# TIDA-01576_ADS8686S_ISO_Interface_Pg7-Co.net
KiCad netlist of a schematic drawn in Altium Designer
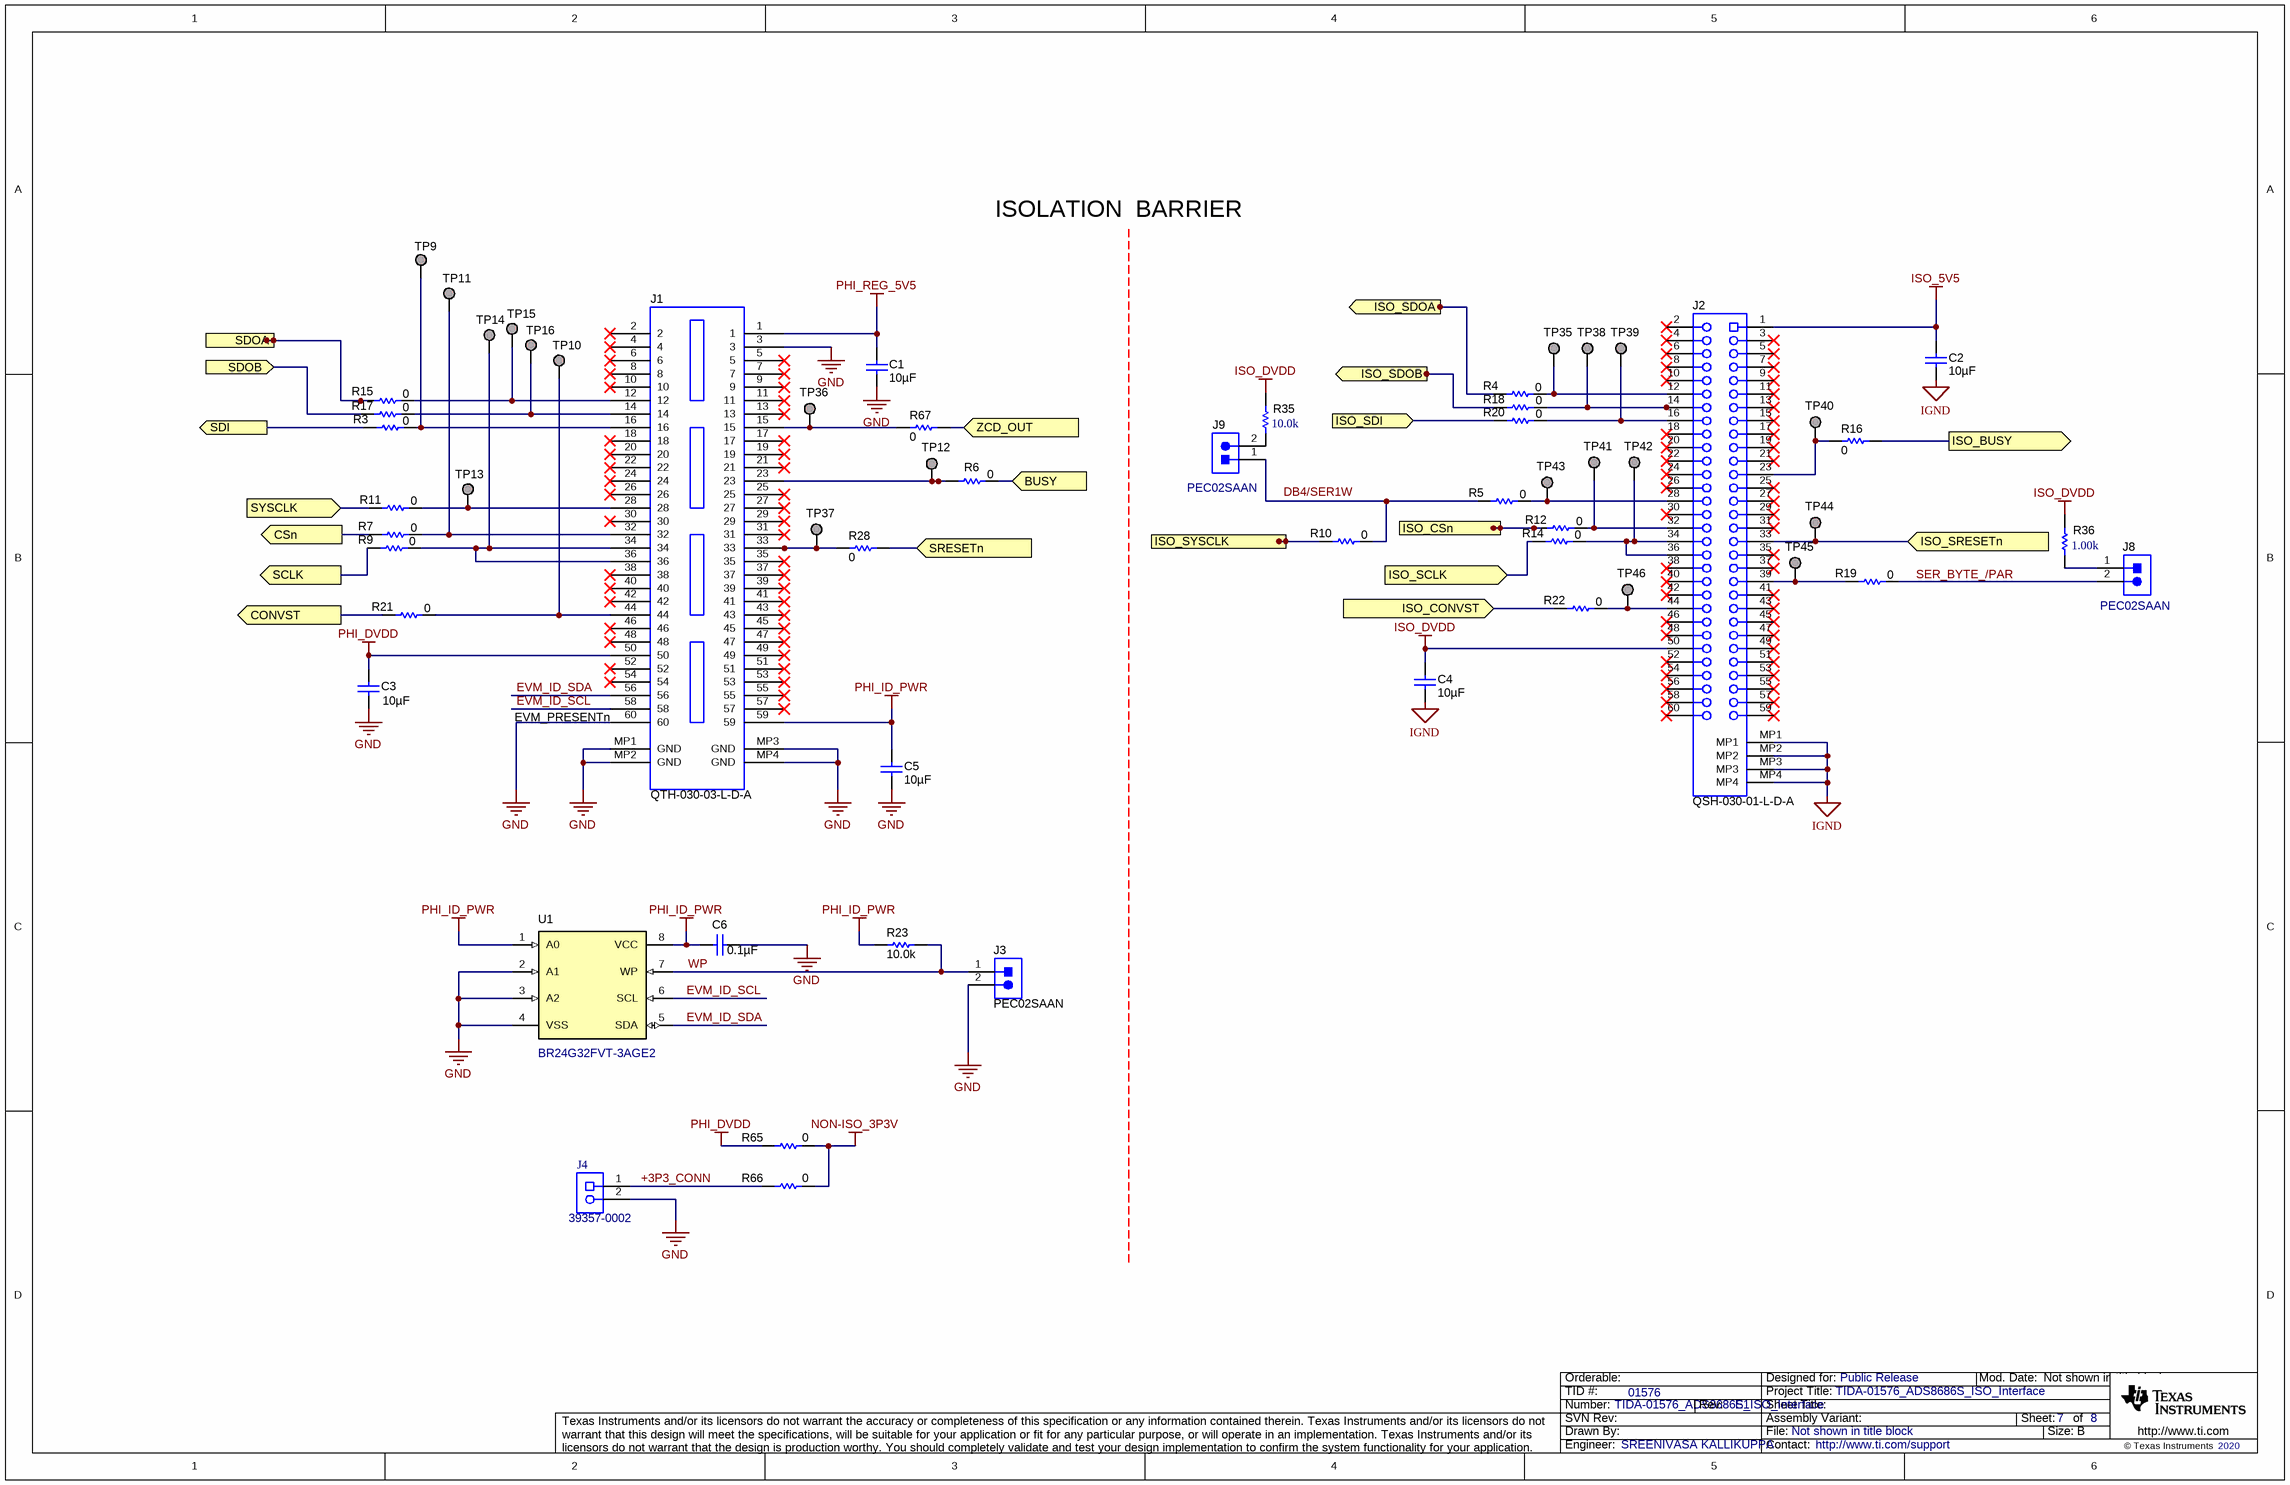
[diagram p0: TIDA-01576_ADS8686S_ISO_Interface_Pg7-Connectors.SchDoc]

(export (version "E")
  (design (tool "Eeschema 10.0.6"))
  (components
    (comp (ref "C1")
      (value "GRM21BR71A106KE51L")
      (footprint "0805_HV")
      (description "CAP, CERM, 10 µF, 10 V, +/- 10%, X7R, 0805")
      (fields
        (field (name "VALUEDISPLAYED") "10µF")
        (field (name "MANUFACTURER") "MuRata")
        (field (name "PUBLISHER") "Texas Instruments")
      )
      (libsource (lib "Capacitor_Ceramic") (part "GRM21BR71A106KE51L"))
    )
    (comp (ref "C2")
      (value "GRM21BR71A106KE51L")
      (footprint "0805_HV")
      (description "CAP, CERM, 10 µF, 10 V, +/- 10%, X7R, 0805")
      (fields
        (field (name "VALUEDISPLAYED") "10µF")
        (field (name "MANUFACTURER") "MuRata")
        (field (name "PUBLISHER") "Texas Instruments")
      )
      (libsource (lib "Capacitor_Ceramic") (part "GRM21BR71A106KE51L"))
    )
    (comp (ref "C3")
      (value "GRM21BR71A106KE51L")
      (footprint "0805_HV")
      (description "CAP, CERM, 10 µF, 10 V, +/- 10%, X7R, 0805")
      (fields
        (field (name "VALUEDISPLAYED") "10µF")
        (field (name "MANUFACTURER") "MuRata")
        (field (name "PUBLISHER") "Texas Instruments")
      )
      (libsource (lib "Capacitor_Ceramic") (part "GRM21BR71A106KE51L"))
    )
    (comp (ref "C4")
      (value "GRM21BR71A106KE51L")
      (footprint "0805_HV")
      (description "CAP, CERM, 10 µF, 10 V, +/- 10%, X7R, 0805")
      (fields
        (field (name "VALUEDISPLAYED") "10µF")
        (field (name "MANUFACTURER") "MuRata")
        (field (name "PUBLISHER") "Texas Instruments")
      )
      (libsource (lib "Capacitor_Ceramic") (part "GRM21BR71A106KE51L"))
    )
    (comp (ref "C5")
      (value "GRM21BR71A106KE51L")
      (footprint "0805_HV")
      (description "CAP, CERM, 10 µF, 10 V, +/- 10%, X7R, 0805")
      (fields
        (field (name "VALUEDISPLAYED") "10µF")
        (field (name "MANUFACTURER") "MuRata")
        (field (name "PUBLISHER") "Texas Instruments")
      )
      (libsource (lib "Capacitor_Ceramic") (part "GRM21BR71A106KE51L"))
    )
    (comp (ref "C6")
      (value "GRM155R71C104KA88D")
      (footprint "0402")
      (description "CAP, CERM, 0.1 µF, 16 V, +/- 10%, X7R, 0402")
      (fields
        (field (name "VALUEDISPLAYED") "0.1µF")
        (field (name "MANUFACTURER") "MuRata")
        (field (name "PUBLISHER") "Texas Instruments")
      )
      (libsource (lib "Capacitor_Ceramic") (part "GRM155R71C104KA88D"))
    )
    (comp (ref "J1")
      (value "QTH-030-03-L-D-A")
      (footprint "Samtec_QTH-030-01-x-D-A")
      (description "Header(Shrouded), 19.7mil, 30x2, Gold, SMT")
      (fields
        (field (name "MANUFACTURER") "Samtec")
        (field (name "SYMBOLCREATOR") "Altium")
        (field (name "PUBLISHER") "Texas Instruments")
      )
      (libsource (lib "Connectors_Samtec") (part "QTH-030-01-L-D-A"))
    )
    (comp (ref "J2")
      (value "QSH-030-01-L-D-A")
      (footprint "Samtec_QSH-030-01-X-D-A")
      (description "Receptacle, 0.5 mm, 30x2, Gold, TH")
      (fields
        (field (name "MANUFACTURER") "Samtec")
        (field (name "SYMBOLCREATOR") "Altium")
        (field (name "PUBLISHER") "Texas Instruments")
      )
      (libsource (lib "Connectors_Samtec") (part "QSH-030-01-L-D-A"))
    )
    (comp (ref "J3")
      (value "PEC02SAAN")
      (footprint "CONN_PEC02SAAN")
      (description "Header, 100mil, 2x1, Tin, TH")
      (fields
        (field (name "MANUFACTURER") "Sullins Connector Solutions")
        (field (name "SYMBOLCREATOR") "a0412235")
        (field (name "PUBLISHER") "Texas Instruments")
      )
      (libsource (lib "Connectors_Sullins") (part "PEC02SAAN"))
    )
    (comp (ref "J4")
      (value "39357-0002")
      (footprint "MOLEX_39357-0002")
      (description "Terminal Block, 3.5 mm, 2x1, Tin, TH")
      (fields (field (name "MANUFACTURER") "Molex") (field (name "PUBLISHER") "Texas Instruments"))
      (libsource (lib "Altium Vault - TI") (part "Receptacle_2x1"))
    )
    (comp (ref "J8")
      (value "PEC02SAAN")
      (footprint "CONN_PEC02SAAN")
      (description "Header, 100mil, 2x1, Tin, TH")
      (fields
        (field (name "MANUFACTURER") "Sullins Connector Solutions")
        (field (name "PUBLISHER") "Texas Instruments")
      )
      (libsource (lib "Altium Vault - TI") (part "Header_2x1"))
    )
    (comp (ref "J9")
      (value "PEC02SAAN")
      (footprint "CONN_PEC02SAAN")
      (description "Header, 100mil, 2x1, Tin, TH")
      (fields
        (field (name "MANUFACTURER") "Sullins Connector Solutions")
        (field (name "PUBLISHER") "Texas Instruments")
      )
      (libsource (lib "") (part "Header_2x1_1"))
    )
    (comp (ref "R3")
      (value "ERJ-2GE0R00X")
      (footprint "0402")
      (description "RES, 0, 5%, 0.063 W, 0402")
      (fields
        (field (name "VALUEDISPLAYED") "0")
        (field (name "MANUFACTURER") "Panasonic")
        (field (name "PUBLISHER") "Texas Instruments")
      )
      (libsource (lib "Resistor_0402") (part "ERJ-2GE0R00X"))
    )
    (comp (ref "R4")
      (value "ERJ-2GE0R00X")
      (footprint "0402")
      (description "RES, 0, 5%, 0.063 W, 0402")
      (fields
        (field (name "VALUEDISPLAYED") "0")
        (field (name "MANUFACTURER") "Panasonic")
        (field (name "PUBLISHER") "Texas Instruments")
      )
      (libsource (lib "Resistor_0402") (part "ERJ-2GE0R00X"))
    )
    (comp (ref "R5")
      (value "ERJ-2GE0R00X")
      (footprint "0402")
      (description "RES, 0, 5%, 0.063 W, 0402")
      (fields
        (field (name "VALUEDISPLAYED") "0")
        (field (name "MANUFACTURER") "Panasonic")
        (field (name "PUBLISHER") "Texas Instruments")
      )
      (libsource (lib "Resistor_0402") (part "ERJ-2GE0R00X"))
    )
    (comp (ref "R6")
      (value "ERJ-2GE0R00X")
      (footprint "0402")
      (description "RES, 0, 5%, 0.063 W, 0402")
      (fields
        (field (name "VALUEDISPLAYED") "0")
        (field (name "MANUFACTURER") "Panasonic")
        (field (name "PUBLISHER") "Texas Instruments")
      )
      (libsource (lib "Resistor_0402") (part "ERJ-2GE0R00X"))
    )
    (comp (ref "R7")
      (value "ERJ-2GE0R00X")
      (footprint "0402")
      (description "RES, 0, 5%, 0.063 W, 0402")
      (fields
        (field (name "VALUEDISPLAYED") "0")
        (field (name "MANUFACTURER") "Panasonic")
        (field (name "PUBLISHER") "Texas Instruments")
      )
      (libsource (lib "Resistor_0402") (part "ERJ-2GE0R00X"))
    )
    (comp (ref "R9")
      (value "ERJ-2GE0R00X")
      (footprint "0402")
      (description "RES, 0, 5%, 0.063 W, 0402")
      (fields
        (field (name "VALUEDISPLAYED") "0")
        (field (name "MANUFACTURER") "Panasonic")
        (field (name "PUBLISHER") "Texas Instruments")
      )
      (libsource (lib "Resistor_0402") (part "ERJ-2GE0R00X"))
    )
    (comp (ref "R10")
      (value "ERJ-2GE0R00X")
      (footprint "0402")
      (description "RES, 0, 5%, 0.063 W, 0402")
      (fields
        (field (name "VALUEDISPLAYED") "0")
        (field (name "MANUFACTURER") "Panasonic")
        (field (name "PUBLISHER") "Texas Instruments")
      )
      (libsource (lib "Resistor_0402") (part "ERJ-2GE0R00X"))
    )
    (comp (ref "R11")
      (value "ERJ-2GE0R00X")
      (footprint "0402")
      (description "RES, 0, 5%, 0.063 W, 0402")
      (fields
        (field (name "VALUEDISPLAYED") "0")
        (field (name "MANUFACTURER") "Panasonic")
        (field (name "PUBLISHER") "Texas Instruments")
      )
      (libsource (lib "Resistor_0402") (part "ERJ-2GE0R00X"))
    )
    (comp (ref "R12")
      (value "ERJ-2GE0R00X")
      (footprint "0402")
      (description "RES, 0, 5%, 0.063 W, 0402")
      (fields
        (field (name "VALUEDISPLAYED") "0")
        (field (name "MANUFACTURER") "Panasonic")
        (field (name "PUBLISHER") "Texas Instruments")
      )
      (libsource (lib "Resistor_0402") (part "ERJ-2GE0R00X"))
    )
    (comp (ref "R14")
      (value "ERJ-2GE0R00X")
      (footprint "0402")
      (description "RES, 0, 5%, 0.063 W, 0402")
      (fields
        (field (name "VALUEDISPLAYED") "0")
        (field (name "MANUFACTURER") "Panasonic")
        (field (name "PUBLISHER") "Texas Instruments")
      )
      (libsource (lib "Resistor_0402") (part "ERJ-2GE0R00X"))
    )
    (comp (ref "R15")
      (value "ERJ-2GE0R00X")
      (footprint "0402")
      (description "RES, 0, 5%, 0.063 W, 0402")
      (fields
        (field (name "VALUEDISPLAYED") "0")
        (field (name "MANUFACTURER") "Panasonic")
        (field (name "PUBLISHER") "Texas Instruments")
      )
      (libsource (lib "Resistor_0402") (part "ERJ-2GE0R00X"))
    )
    (comp (ref "R16")
      (value "ERJ-2GE0R00X")
      (footprint "0402")
      (description "RES, 0, 5%, 0.063 W, 0402")
      (fields
        (field (name "VALUEDISPLAYED") "0")
        (field (name "MANUFACTURER") "Panasonic")
        (field (name "PUBLISHER") "Texas Instruments")
      )
      (libsource (lib "Resistor_0402") (part "ERJ-2GE0R00X"))
    )
    (comp (ref "R17")
      (value "ERJ-2GE0R00X")
      (footprint "0402")
      (description "RES, 0, 5%, 0.063 W, 0402")
      (fields
        (field (name "VALUEDISPLAYED") "0")
        (field (name "MANUFACTURER") "Panasonic")
        (field (name "PUBLISHER") "Texas Instruments")
      )
      (libsource (lib "Resistor_0402") (part "ERJ-2GE0R00X"))
    )
    (comp (ref "R18")
      (value "ERJ-2GE0R00X")
      (footprint "0402")
      (description "RES, 0, 5%, 0.063 W, 0402")
      (fields
        (field (name "VALUEDISPLAYED") "0")
        (field (name "MANUFACTURER") "Panasonic")
        (field (name "PUBLISHER") "Texas Instruments")
      )
      (libsource (lib "Resistor_0402") (part "ERJ-2GE0R00X"))
    )
    (comp (ref "R19")
      (value "ERJ-2GE0R00X")
      (footprint "0402")
      (description "RES, 0, 5%, 0.063 W, 0402")
      (fields
        (field (name "VALUEDISPLAYED") "0")
        (field (name "MANUFACTURER") "Panasonic")
        (field (name "PUBLISHER") "Texas Instruments")
      )
      (libsource (lib "Resistor_0402") (part "ERJ-2GE0R00X"))
    )
    (comp (ref "R20")
      (value "ERJ-2GE0R00X")
      (footprint "0402")
      (description "RES, 0, 5%, 0.063 W, 0402")
      (fields
        (field (name "VALUEDISPLAYED") "0")
        (field (name "MANUFACTURER") "Panasonic")
        (field (name "PUBLISHER") "Texas Instruments")
      )
      (libsource (lib "Resistor_0402") (part "ERJ-2GE0R00X"))
    )
    (comp (ref "R21")
      (value "ERJ-2GE0R00X")
      (footprint "0402")
      (description "RES, 0, 5%, 0.063 W, 0402")
      (fields
        (field (name "VALUEDISPLAYED") "0")
        (field (name "MANUFACTURER") "Panasonic")
        (field (name "PUBLISHER") "Texas Instruments")
      )
      (libsource (lib "Resistor_0402") (part "ERJ-2GE0R00X"))
    )
    (comp (ref "R22")
      (value "ERJ-2GE0R00X")
      (footprint "0402")
      (description "RES, 0, 5%, 0.063 W, 0402")
      (fields
        (field (name "VALUEDISPLAYED") "0")
        (field (name "MANUFACTURER") "Panasonic")
        (field (name "PUBLISHER") "Texas Instruments")
      )
      (libsource (lib "Resistor_0402") (part "ERJ-2GE0R00X"))
    )
    (comp (ref "R23")
      (value "CRCW060310K0FKEA")
      (footprint "0603")
      (description "RES, 10.0 k, 1%, 0.1 W, 0603")
      (fields
        (field (name "VALUEDISPLAYED") "10.0k")
        (field (name "MANUFACTURER") "Vishay-Dale")
        (field (name "PUBLISHER") "Texas Instruments")
      )
      (libsource (lib "Resistor_0603") (part "CRCW060310K0FKEA"))
    )
    (comp (ref "R28")
      (value "ERJ-2GE0R00X")
      (footprint "0402")
      (description "RES, 0, 5%, 0.063 W, 0402")
      (fields
        (field (name "VALUEDISPLAYED") "0")
        (field (name "MANUFACTURER") "Panasonic")
        (field (name "PUBLISHER") "Texas Instruments")
      )
      (libsource (lib "Resistor_0402") (part "ERJ-2GE0R00X"))
    )
    (comp (ref "R35")
      (value "ERJ-2RKF1002X")
      (footprint "0402")
      (description "RES, 10.0 k, 1%, 0.1 W, 0402")
      (fields
        (field (name "MANUFACTURER") "Panasonic")
        (field (name "VALUEDISPLAYED") "10.0k")
        (field (name "PUBLISHER") "Texas Instruments")
      )
      (libsource (lib "Altium Vault - TI") (part "Resistor"))
    )
    (comp (ref "R36")
      (value "ERJ-2RKF1001X")
      (footprint "0402")
      (description "RES, 1.00 k, 1%, 0.1 W, 0402")
      (fields
        (field (name "MANUFACTURER") "Panasonic")
        (field (name "VALUEDISPLAYED") "1.00k")
        (field (name "PUBLISHER") "Texas Instruments")
      )
      (libsource (lib "Altium Vault - TI") (part "Resistor"))
    )
    (comp (ref "R65")
      (value "CRCW06030000Z0EA")
      (footprint "0603")
      (description "RES, 0, 5%, 0.1 W, 0603")
      (fields
        (field (name "VALUEDISPLAYED") "0")
        (field (name "MANUFACTURER") "Vishay-Dale")
        (field (name "PUBLISHER") "Texas Instruments")
      )
      (libsource (lib "Resistor_0603") (part "CRCW06030000Z0EA"))
    )
    (comp (ref "R66")
      (value "CRCW06030000Z0EA")
      (footprint "0603")
      (description "RES, 0, 5%, 0.1 W, 0603")
      (fields
        (field (name "VALUEDISPLAYED") "0")
        (field (name "MANUFACTURER") "Vishay-Dale")
        (field (name "PUBLISHER") "Texas Instruments")
      )
      (libsource (lib "Resistor_0603") (part "CRCW06030000Z0EA"))
    )
    (comp (ref "R67")
      (value "ERJ-2GE0R00X")
      (footprint "0402")
      (description "RES, 0, 5%, 0.063 W, 0402")
      (fields
        (field (name "VALUEDISPLAYED") "0")
        (field (name "MANUFACTURER") "Panasonic")
        (field (name "PUBLISHER") "Texas Instruments")
      )
      (libsource (lib "Resistor_0402") (part "ERJ-2GE0R00X"))
    )
    (comp (ref "TP9")
      (value "TP_H0.45P0.75")
      (footprint "TP_H045P075")
      (description "Testpoint")
      (fields
        (field (name "MANUFACTURER") "Texas Instruments")
        (field (name "SYMBOLCREATOR") "a0412235")
        (field (name "PUBLISHER") "Texas Instruments")
      )
      (libsource (lib "Hardware") (part "TP_H0.45P0.75"))
    )
    (comp (ref "TP10")
      (value "TP_H0.45P0.75")
      (footprint "TP_H045P075")
      (description "Testpoint")
      (fields
        (field (name "MANUFACTURER") "Texas Instruments")
        (field (name "SYMBOLCREATOR") "a0412235")
        (field (name "PUBLISHER") "Texas Instruments")
      )
      (libsource (lib "Hardware") (part "TP_H0.45P0.75"))
    )
    (comp (ref "TP11")
      (value "TP_H0.45P0.75")
      (footprint "TP_H045P075")
      (description "Testpoint")
      (fields
        (field (name "MANUFACTURER") "Texas Instruments")
        (field (name "SYMBOLCREATOR") "a0412235")
        (field (name "PUBLISHER") "Texas Instruments")
      )
      (libsource (lib "Hardware") (part "TP_H0.45P0.75"))
    )
    (comp (ref "TP12")
      (value "TP_H0.45P0.75")
      (footprint "TP_H045P075")
      (description "Testpoint")
      (fields
        (field (name "MANUFACTURER") "Texas Instruments")
        (field (name "SYMBOLCREATOR") "a0412235")
        (field (name "PUBLISHER") "Texas Instruments")
      )
      (libsource (lib "Hardware") (part "TP_H0.45P0.75"))
    )
    (comp (ref "TP13")
      (value "TP_H0.45P0.75")
      (footprint "TP_H045P075")
      (description "Testpoint")
      (fields
        (field (name "MANUFACTURER") "Texas Instruments")
        (field (name "SYMBOLCREATOR") "a0412235")
        (field (name "PUBLISHER") "Texas Instruments")
      )
      (libsource (lib "Hardware") (part "TP_H0.45P0.75"))
    )
    (comp (ref "TP14")
      (value "TP_H0.45P0.75")
      (footprint "TP_H045P075")
      (description "Testpoint")
      (fields
        (field (name "MANUFACTURER") "Texas Instruments")
        (field (name "SYMBOLCREATOR") "a0412235")
        (field (name "PUBLISHER") "Texas Instruments")
      )
      (libsource (lib "Hardware") (part "TP_H0.45P0.75"))
    )
    (comp (ref "TP15")
      (value "TP_H0.45P0.75")
      (footprint "TP_H045P075")
      (description "Testpoint")
      (fields
        (field (name "MANUFACTURER") "Texas Instruments")
        (field (name "SYMBOLCREATOR") "a0412235")
        (field (name "PUBLISHER") "Texas Instruments")
      )
      (libsource (lib "Hardware") (part "TP_H0.45P0.75"))
    )
    (comp (ref "TP16")
      (value "TP_H0.45P0.75")
      (footprint "TP_H045P075")
      (description "Testpoint")
      (fields
        (field (name "MANUFACTURER") "Texas Instruments")
        (field (name "SYMBOLCREATOR") "a0412235")
        (field (name "PUBLISHER") "Texas Instruments")
      )
      (libsource (lib "Hardware") (part "TP_H0.45P0.75"))
    )
    (comp (ref "TP35")
      (value "TP_H0.45P0.75")
      (footprint "TP_H045P075")
      (description "Testpoint")
      (fields
        (field (name "MANUFACTURER") "Texas Instruments")
        (field (name "SYMBOLCREATOR") "a0412235")
        (field (name "PUBLISHER") "Texas Instruments")
      )
      (libsource (lib "Hardware") (part "TP_H0.45P0.75"))
    )
    (comp (ref "TP36")
      (value "TP_H0.45P0.75")
      (footprint "TP_H045P075")
      (description "Testpoint")
      (fields
        (field (name "MANUFACTURER") "Texas Instruments")
        (field (name "SYMBOLCREATOR") "a0412235")
        (field (name "PUBLISHER") "Texas Instruments")
      )
      (libsource (lib "Hardware") (part "TP_H0.45P0.75"))
    )
    (comp (ref "TP37")
      (value "TP_H0.45P0.75")
      (footprint "TP_H045P075")
      (description "Testpoint")
      (fields
        (field (name "MANUFACTURER") "Texas Instruments")
        (field (name "SYMBOLCREATOR") "a0412235")
        (field (name "PUBLISHER") "Texas Instruments")
      )
      (libsource (lib "Hardware") (part "TP_H0.45P0.75"))
    )
    (comp (ref "TP38")
      (value "TP_H0.45P0.75")
      (footprint "TP_H045P075")
      (description "Testpoint")
      (fields
        (field (name "MANUFACTURER") "Texas Instruments")
        (field (name "SYMBOLCREATOR") "a0412235")
        (field (name "PUBLISHER") "Texas Instruments")
      )
      (libsource (lib "Hardware") (part "TP_H0.45P0.75"))
    )
    (comp (ref "TP39")
      (value "TP_H0.45P0.75")
      (footprint "TP_H045P075")
      (description "Testpoint")
      (fields
        (field (name "MANUFACTURER") "Texas Instruments")
        (field (name "SYMBOLCREATOR") "a0412235")
        (field (name "PUBLISHER") "Texas Instruments")
      )
      (libsource (lib "Hardware") (part "TP_H0.45P0.75"))
    )
    (comp (ref "TP40")
      (value "TP_H0.45P0.75")
      (footprint "TP_H045P075")
      (description "Testpoint")
      (fields
        (field (name "MANUFACTURER") "Texas Instruments")
        (field (name "SYMBOLCREATOR") "a0412235")
        (field (name "PUBLISHER") "Texas Instruments")
      )
      (libsource (lib "Hardware") (part "TP_H0.45P0.75"))
    )
    (comp (ref "TP41")
      (value "TP_H0.45P0.75")
      (footprint "TP_H045P075")
      (description "Testpoint")
      (fields
        (field (name "MANUFACTURER") "Texas Instruments")
        (field (name "SYMBOLCREATOR") "a0412235")
        (field (name "PUBLISHER") "Texas Instruments")
      )
      (libsource (lib "Hardware") (part "TP_H0.45P0.75"))
    )
    (comp (ref "TP42")
      (value "TP_H0.45P0.75")
      (footprint "TP_H045P075")
      (description "Testpoint")
      (fields
        (field (name "MANUFACTURER") "Texas Instruments")
        (field (name "SYMBOLCREATOR") "a0412235")
        (field (name "PUBLISHER") "Texas Instruments")
      )
      (libsource (lib "Hardware") (part "TP_H0.45P0.75"))
    )
    (comp (ref "TP43")
      (value "TP_H0.45P0.75")
      (footprint "TP_H045P075")
      (description "Testpoint")
      (fields
        (field (name "MANUFACTURER") "Texas Instruments")
        (field (name "SYMBOLCREATOR") "a0412235")
        (field (name "PUBLISHER") "Texas Instruments")
      )
      (libsource (lib "Hardware") (part "TP_H0.45P0.75"))
    )
    (comp (ref "TP44")
      (value "TP_H0.45P0.75")
      (footprint "TP_H045P075")
      (description "Testpoint")
      (fields
        (field (name "MANUFACTURER") "Texas Instruments")
        (field (name "SYMBOLCREATOR") "a0412235")
        (field (name "PUBLISHER") "Texas Instruments")
      )
      (libsource (lib "Hardware") (part "TP_H0.45P0.75"))
    )
    (comp (ref "TP45")
      (value "TP_H0.45P0.75")
      (footprint "TP_H045P075")
      (description "Testpoint")
      (fields
        (field (name "MANUFACTURER") "Texas Instruments")
        (field (name "SYMBOLCREATOR") "a0412235")
        (field (name "PUBLISHER") "Texas Instruments")
      )
      (libsource (lib "Hardware") (part "TP_H0.45P0.75"))
    )
    (comp (ref "TP46")
      (value "TP_H0.45P0.75")
      (footprint "TP_H045P075")
      (description "Testpoint")
      (fields
        (field (name "MANUFACTURER") "Texas Instruments")
        (field (name "SYMBOLCREATOR") "a0412235")
        (field (name "PUBLISHER") "Texas Instruments")
      )
      (libsource (lib "Hardware") (part "TP_H0.45P0.75"))
    )
    (comp (ref "U1")
      (value "BR24G32FVT-3AGE2")
      (footprint "TSOP65P640X120-8N")
      (description "I2C BUS EEPROM (2-Wire), TSSOP-B8")
      (fields (field (name "MANUFACTURER") "Rohm") (field (name "PUBLISHER") "Texas Instruments"))
      (libsource (lib "Altium Vault - TI") (part "EEPROM_8P"))
    )
  )
  (nets
    (net (code "1") (name "/+3P3_CONN") (class "Default")
      (node (ref "J4") (pin "1") (pinfunction "1_1") (pintype "passive"))
      (node (ref "R66") (pin "2") (pinfunction "2_2") (pintype "passive"))
    )
    (net (code "2") (name "/BUSY") (class "Default")
      (node (ref "R6") (pin "2") (pinfunction "2_2") (pintype "passive"))
    )
    (net (code "3") (name "/CONVST") (class "Default")
      (node (ref "R21") (pin "1") (pinfunction "1_1") (pintype "passive"))
    )
    (net (code "4") (name "/CSn") (class "Default")
      (node (ref "R7") (pin "1") (pinfunction "1_1") (pintype "passive"))
    )
    (net (code "6") (name "/EVM_ID_SCL") (class "Default")
      (node (ref "J1") (pin "58") (pinfunction "58_58") (pintype "passive"))
      (node (ref "U1") (pin "6") (pinfunction "SCL_6") (pintype "input"))
    )
    (net (code "7") (name "/EVM_ID_SDA") (class "Default")
      (node (ref "J1") (pin "56") (pinfunction "56_56") (pintype "passive"))
      (node (ref "U1") (pin "5") (pinfunction "SDA_5") (pintype "bidirectional"))
    )
    (net (code "8") (name "/ISO_BUSY") (class "Default")
      (node (ref "R16") (pin "1") (pinfunction "1_1") (pintype "passive"))
    )
    (net (code "9") (name "/ISO_CONVST") (class "Default")
      (node (ref "R22") (pin "1") (pinfunction "1_1") (pintype "passive"))
    )
    (net (code "10") (name "/ISO_CSn") (class "Default")
      (node (ref "R12") (pin "1") (pinfunction "1_1") (pintype "passive"))
    )
    (net (code "11") (name "/ISO_SCLK") (class "Default")
      (node (ref "R14") (pin "1") (pinfunction "1_1") (pintype "passive"))
    )
    (net (code "12") (name "/ISO_SDI") (class "Default")
      (node (ref "R20") (pin "1") (pinfunction "1_1") (pintype "passive"))
    )
    (net (code "13") (name "/ISO_SDOA") (class "Default")
      (node (ref "R4") (pin "1") (pinfunction "1_1") (pintype "passive"))
    )
    (net (code "14") (name "/ISO_SDOB") (class "Default")
      (node (ref "R18") (pin "1") (pinfunction "1_1") (pintype "passive"))
    )
    (net (code "15") (name "/ISO_SRESETn") (class "Default")
      (node (ref "J2") (pin "33") (pinfunction "33_33") (pintype "passive"))
      (node (ref "TP44") (pin "1") (pintype "passive"))
    )
    (net (code "16") (name "/ISO_SYSCLK") (class "Default")
      (node (ref "R10") (pin "1") (pinfunction "1_1") (pintype "passive"))
    )
    (net (code "17") (name "/SCLK") (class "Default")
      (node (ref "R9") (pin "1") (pinfunction "1_1") (pintype "passive"))
    )
    (net (code "18") (name "/SDI") (class "Default")
      (node (ref "R3") (pin "1") (pinfunction "1_1") (pintype "passive"))
    )
    (net (code "19") (name "/SDOA") (class "Default")
      (node (ref "R15") (pin "1") (pinfunction "1_1") (pintype "passive"))
    )
    (net (code "20") (name "/SDOB") (class "Default")
      (node (ref "R17") (pin "1") (pinfunction "1_1") (pintype "passive"))
    )
    (net (code "22") (name "/SRESETn") (class "Default")
      (node (ref "R28") (pin "1") (pinfunction "1_1") (pintype "passive"))
    )
    (net (code "23") (name "/SYSCLK") (class "Default")
      (node (ref "R11") (pin "1") (pinfunction "1_1") (pintype "passive"))
    )
    (net (code "24") (name "/WP") (class "Default")
      (node (ref "J3") (pin "1") (pinfunction "1_1") (pintype "passive"))
      (node (ref "R23") (pin "1") (pinfunction "1_1") (pintype "passive"))
      (node (ref "U1") (pin "7") (pinfunction "WP_7") (pintype "input"))
    )
    (net (code "25") (name "/ZCD_OUT") (class "Default")
      (node (ref "R67") (pin "1") (pinfunction "1_1") (pintype "passive"))
    )
    (net (code "26") (name "GND") (class "Default")
      (node (ref "C1") (pin "2") (pinfunction "2_2") (pintype "passive"))
      (node (ref "C3") (pin "2") (pinfunction "2_2") (pintype "passive"))
      (node (ref "C5") (pin "2") (pinfunction "2_2") (pintype "passive"))
      (node (ref "C6") (pin "1") (pinfunction "1_1") (pintype "passive"))
      (node (ref "J1") (pin "3") (pinfunction "3_3") (pintype "passive"))
      (node (ref "J1") (pin "60") (pinfunction "60_60") (pintype "passive"))
      (node (ref "J1") (pin "MP1") (pinfunction "GND_MP1") (pintype "passive"))
      (node (ref "J1") (pin "MP2") (pinfunction "GND_MP2") (pintype "passive"))
      (node (ref "J1") (pin "MP3") (pinfunction "GND_MP3") (pintype "passive"))
      (node (ref "J1") (pin "MP4") (pinfunction "GND_MP4") (pintype "passive"))
      (node (ref "J3") (pin "2") (pinfunction "2_2") (pintype "passive"))
      (node (ref "J4") (pin "2") (pinfunction "2_2") (pintype "passive"))
      (node (ref "U1") (pin "2") (pinfunction "A1_2") (pintype "input"))
      (node (ref "U1") (pin "3") (pinfunction "A2_3") (pintype "input"))
      (node (ref "U1") (pin "4") (pinfunction "VSS_4") (pintype "power_in"))
    )
    (net (code "27") (name "IGND") (class "Default")
      (node (ref "C2") (pin "2") (pinfunction "2_2") (pintype "passive"))
      (node (ref "C4") (pin "2") (pinfunction "2_2") (pintype "passive"))
      (node (ref "J2") (pin "MP1") (pinfunction "MP1_MP1") (pintype "passive"))
      (node (ref "J2") (pin "MP2") (pinfunction "MP2_MP2") (pintype "passive"))
      (node (ref "J2") (pin "MP3") (pinfunction "MP3_MP3") (pintype "passive"))
      (node (ref "J2") (pin "MP4") (pinfunction "MP4_MP4") (pintype "passive"))
    )
    (net (code "28") (name "ISO_5V5") (class "Default")
      (node (ref "C2") (pin "1") (pinfunction "1_1") (pintype "passive"))
      (node (ref "J2") (pin "1") (pinfunction "1_1") (pintype "passive"))
    )
    (net (code "29") (name "ISO_DVDD") (class "Default")
      (node (ref "C4") (pin "1") (pinfunction "1_1") (pintype "passive"))
      (node (ref "J2") (pin "50") (pinfunction "50_50") (pintype "passive"))
      (node (ref "R35") (pin "2") (pinfunction "2_2") (pintype "passive"))
      (node (ref "R36") (pin "2") (pinfunction "2_2") (pintype "passive"))
    )
    (net (code "30") (name "NON-ISO_3P3V") (class "Default")
      (node (ref "R65") (pin "1") (pinfunction "1_1") (pintype "passive"))
      (node (ref "R66") (pin "1") (pinfunction "1_1") (pintype "passive"))
    )
    (net (code "31") (name "Net-(J1-Pad12)") (class "Default")
      (node (ref "J1") (pin "12") (pinfunction "12_12") (pintype "passive"))
      (node (ref "R15") (pin "2") (pinfunction "2_2") (pintype "passive"))
      (node (ref "TP15") (pin "1") (pintype "passive"))
    )
    (net (code "32") (name "Net-(J1-Pad14)") (class "Default")
      (node (ref "J1") (pin "14") (pinfunction "14_14") (pintype "passive"))
      (node (ref "R17") (pin "2") (pinfunction "2_2") (pintype "passive"))
      (node (ref "TP16") (pin "1") (pintype "passive"))
    )
    (net (code "33") (name "Net-(J1-Pad15)") (class "Default")
      (node (ref "J1") (pin "15") (pinfunction "15_15") (pintype "passive"))
      (node (ref "R67") (pin "2") (pinfunction "2_2") (pintype "passive"))
      (node (ref "TP36") (pin "1") (pintype "passive"))
    )
    (net (code "34") (name "Net-(J1-Pad16)") (class "Default")
      (node (ref "J1") (pin "16") (pinfunction "16_16") (pintype "passive"))
      (node (ref "R3") (pin "2") (pinfunction "2_2") (pintype "passive"))
      (node (ref "TP9") (pin "1") (pintype "passive"))
    )
    (net (code "35") (name "Net-(J1-Pad23)") (class "Default")
      (node (ref "J1") (pin "23") (pinfunction "23_23") (pintype "passive"))
      (node (ref "R6") (pin "1") (pinfunction "1_1") (pintype "passive"))
      (node (ref "TP12") (pin "1") (pintype "passive"))
    )
    (net (code "36") (name "Net-(J1-Pad28)") (class "Default")
      (node (ref "J1") (pin "28") (pinfunction "28_28") (pintype "passive"))
      (node (ref "R11") (pin "2") (pinfunction "2_2") (pintype "passive"))
      (node (ref "TP13") (pin "1") (pintype "passive"))
    )
    (net (code "37") (name "Net-(J1-Pad32)") (class "Default")
      (node (ref "J1") (pin "32") (pinfunction "32_32") (pintype "passive"))
      (node (ref "R7") (pin "2") (pinfunction "2_2") (pintype "passive"))
      (node (ref "TP11") (pin "1") (pintype "passive"))
    )
    (net (code "38") (name "Net-(J1-Pad33)") (class "Default")
      (node (ref "J1") (pin "33") (pinfunction "33_33") (pintype "passive"))
      (node (ref "R28") (pin "2") (pinfunction "2_2") (pintype "passive"))
      (node (ref "TP37") (pin "1") (pintype "passive"))
    )
    (net (code "39") (name "Net-(J1-Pad34)") (class "Default")
      (node (ref "J1") (pin "34") (pinfunction "34_34") (pintype "passive"))
      (node (ref "J1") (pin "36") (pinfunction "36_36") (pintype "passive"))
      (node (ref "R9") (pin "2") (pinfunction "2_2") (pintype "passive"))
      (node (ref "TP14") (pin "1") (pintype "passive"))
    )
    (net (code "40") (name "Net-(J1-Pad44)") (class "Default")
      (node (ref "J1") (pin "44") (pinfunction "44_44") (pintype "passive"))
      (node (ref "R21") (pin "2") (pinfunction "2_2") (pintype "passive"))
      (node (ref "TP10") (pin "1") (pintype "passive"))
    )
    (net (code "41") (name "Net-(J2-Pad12)") (class "Default")
      (node (ref "J2") (pin "12") (pinfunction "12_12") (pintype "passive"))
      (node (ref "R4") (pin "2") (pinfunction "2_2") (pintype "passive"))
      (node (ref "TP35") (pin "1") (pintype "passive"))
    )
    (net (code "42") (name "Net-(J2-Pad14)") (class "Default")
      (node (ref "J2") (pin "14") (pinfunction "14_14") (pintype "passive"))
      (node (ref "R18") (pin "2") (pinfunction "2_2") (pintype "passive"))
      (node (ref "TP38") (pin "1") (pintype "passive"))
    )
    (net (code "43") (name "Net-(J2-Pad16)") (class "Default")
      (node (ref "J2") (pin "16") (pinfunction "16_16") (pintype "passive"))
      (node (ref "R20") (pin "2") (pinfunction "2_2") (pintype "passive"))
      (node (ref "TP39") (pin "1") (pintype "passive"))
    )
    (net (code "44") (name "Net-(J2-Pad23)") (class "Default")
      (node (ref "J2") (pin "23") (pinfunction "23_23") (pintype "passive"))
      (node (ref "R16") (pin "2") (pinfunction "2_2") (pintype "passive"))
      (node (ref "TP40") (pin "1") (pintype "passive"))
    )
    (net (code "45") (name "Net-(J2-Pad28)") (class "Default")
      (node (ref "J2") (pin "28") (pinfunction "28_28") (pintype "passive"))
      (node (ref "R5") (pin "2") (pinfunction "2_2") (pintype "passive"))
      (node (ref "TP43") (pin "1") (pintype "passive"))
    )
    (net (code "46") (name "Net-(J2-Pad32)") (class "Default")
      (node (ref "J2") (pin "32") (pinfunction "32_32") (pintype "passive"))
      (node (ref "R12") (pin "2") (pinfunction "2_2") (pintype "passive"))
      (node (ref "TP41") (pin "1") (pintype "passive"))
    )
    (net (code "47") (name "Net-(J2-Pad34)") (class "Default")
      (node (ref "J2") (pin "34") (pinfunction "34_34") (pintype "passive"))
      (node (ref "J2") (pin "36") (pinfunction "36_36") (pintype "passive"))
      (node (ref "R14") (pin "2") (pinfunction "2_2") (pintype "passive"))
      (node (ref "TP42") (pin "1") (pintype "passive"))
    )
    (net (code "48") (name "Net-(J2-Pad39)") (class "Default")
      (node (ref "J2") (pin "39") (pinfunction "39_39") (pintype "passive"))
      (node (ref "R19") (pin "1") (pinfunction "1_1") (pintype "passive"))
      (node (ref "TP45") (pin "1") (pintype "passive"))
    )
    (net (code "49") (name "Net-(J2-Pad44)") (class "Default")
      (node (ref "J2") (pin "44") (pinfunction "44_44") (pintype "passive"))
      (node (ref "R22") (pin "2") (pinfunction "2_2") (pintype "passive"))
      (node (ref "TP46") (pin "1") (pintype "passive"))
    )
    (net (code "50") (name "Net-(J8-Pad1)") (class "Default")
      (node (ref "J8") (pin "1") (pinfunction "1_1") (pintype "passive"))
      (node (ref "R36") (pin "1") (pinfunction "1_1") (pintype "passive"))
    )
    (net (code "51") (name "Net-(J8-Pad2)") (class "Default")
      (node (ref "J8") (pin "2") (pinfunction "2_2") (pintype "passive"))
      (node (ref "R19") (pin "2") (pinfunction "2_2") (pintype "passive"))
    )
    (net (code "52") (name "Net-(J9-Pad1)") (class "Default")
      (node (ref "J9") (pin "1") (pinfunction "1_1") (pintype "passive"))
      (node (ref "R10") (pin "2") (pinfunction "2_2") (pintype "passive"))
      (node (ref "R5") (pin "1") (pinfunction "1_1") (pintype "passive"))
    )
    (net (code "53") (name "Net-(J9-Pad2)") (class "Default")
      (node (ref "J9") (pin "2") (pinfunction "2_2") (pintype "passive"))
      (node (ref "R35") (pin "1") (pinfunction "1_1") (pintype "passive"))
    )
    (net (code "54") (name "PHI_DVDD") (class "Default")
      (node (ref "C3") (pin "1") (pinfunction "1_1") (pintype "passive"))
      (node (ref "J1") (pin "50") (pinfunction "50_50") (pintype "passive"))
      (node (ref "R65") (pin "2") (pinfunction "2_2") (pintype "passive"))
    )
    (net (code "55") (name "PHI_ID_PWR") (class "Default")
      (node (ref "C5") (pin "1") (pinfunction "1_1") (pintype "passive"))
      (node (ref "C6") (pin "2") (pinfunction "2_2") (pintype "passive"))
      (node (ref "J1") (pin "59") (pinfunction "59_59") (pintype "passive"))
      (node (ref "R23") (pin "2") (pinfunction "2_2") (pintype "passive"))
      (node (ref "U1") (pin "1") (pinfunction "A0_1") (pintype "input"))
      (node (ref "U1") (pin "8") (pinfunction "VCC_8") (pintype "power_in"))
    )
    (net (code "56") (name "PHI_REG_5V5") (class "Default")
      (node (ref "C1") (pin "1") (pinfunction "1_1") (pintype "passive"))
      (node (ref "J1") (pin "1") (pinfunction "1_1") (pintype "passive"))
    )
    (net (code "57") (name "unconnected-(J1-Pad2)") (class "Default")
      (node (ref "J1") (pin "2") (pinfunction "2_2") (pintype "passive+no_connect"))
    )
    (net (code "58") (name "unconnected-(J1-Pad4)") (class "Default")
      (node (ref "J1") (pin "4") (pinfunction "4_4") (pintype "passive+no_connect"))
    )
    (net (code "59") (name "unconnected-(J1-Pad5)") (class "Default")
      (node (ref "J1") (pin "5") (pinfunction "5_5") (pintype "passive+no_connect"))
    )
    (net (code "60") (name "unconnected-(J1-Pad6)") (class "Default")
      (node (ref "J1") (pin "6") (pinfunction "6_6") (pintype "passive+no_connect"))
    )
    (net (code "61") (name "unconnected-(J1-Pad7)") (class "Default")
      (node (ref "J1") (pin "7") (pinfunction "7_7") (pintype "passive+no_connect"))
    )
    (net (code "62") (name "unconnected-(J1-Pad8)") (class "Default")
      (node (ref "J1") (pin "8") (pinfunction "8_8") (pintype "passive+no_connect"))
    )
    (net (code "63") (name "unconnected-(J1-Pad9)") (class "Default")
      (node (ref "J1") (pin "9") (pinfunction "9_9") (pintype "passive+no_connect"))
    )
    (net (code "64") (name "unconnected-(J1-Pad10)") (class "Default")
      (node (ref "J1") (pin "10") (pinfunction "10_10") (pintype "passive+no_connect"))
    )
    (net (code "65") (name "unconnected-(J1-Pad11)") (class "Default")
      (node (ref "J1") (pin "11") (pinfunction "11_11") (pintype "passive+no_connect"))
    )
    (net (code "66") (name "unconnected-(J1-Pad13)") (class "Default")
      (node (ref "J1") (pin "13") (pinfunction "13_13") (pintype "passive+no_connect"))
    )
    (net (code "67") (name "unconnected-(J1-Pad17)") (class "Default")
      (node (ref "J1") (pin "17") (pinfunction "17_17") (pintype "passive+no_connect"))
    )
    (net (code "68") (name "unconnected-(J1-Pad18)") (class "Default")
      (node (ref "J1") (pin "18") (pinfunction "18_18") (pintype "passive+no_connect"))
    )
    (net (code "69") (name "unconnected-(J1-Pad19)") (class "Default")
      (node (ref "J1") (pin "19") (pinfunction "19_19") (pintype "passive+no_connect"))
    )
    (net (code "70") (name "unconnected-(J1-Pad20)") (class "Default")
      (node (ref "J1") (pin "20") (pinfunction "20_20") (pintype "passive+no_connect"))
    )
    (net (code "71") (name "unconnected-(J1-Pad21)") (class "Default")
      (node (ref "J1") (pin "21") (pinfunction "21_21") (pintype "passive+no_connect"))
    )
    (net (code "72") (name "unconnected-(J1-Pad22)") (class "Default")
      (node (ref "J1") (pin "22") (pinfunction "22_22") (pintype "passive+no_connect"))
    )
    (net (code "73") (name "unconnected-(J1-Pad24)") (class "Default")
      (node (ref "J1") (pin "24") (pinfunction "24_24") (pintype "passive+no_connect"))
    )
    (net (code "74") (name "unconnected-(J1-Pad25)") (class "Default")
      (node (ref "J1") (pin "25") (pinfunction "25_25") (pintype "passive+no_connect"))
    )
    (net (code "75") (name "unconnected-(J1-Pad26)") (class "Default")
      (node (ref "J1") (pin "26") (pinfunction "26_26") (pintype "passive+no_connect"))
    )
    (net (code "76") (name "unconnected-(J1-Pad27)") (class "Default")
      (node (ref "J1") (pin "27") (pinfunction "27_27") (pintype "passive+no_connect"))
    )
    (net (code "77") (name "unconnected-(J1-Pad29)") (class "Default")
      (node (ref "J1") (pin "29") (pinfunction "29_29") (pintype "passive+no_connect"))
    )
    (net (code "78") (name "unconnected-(J1-Pad30)") (class "Default")
      (node (ref "J1") (pin "30") (pinfunction "30_30") (pintype "passive+no_connect"))
    )
    (net (code "79") (name "unconnected-(J1-Pad31)") (class "Default")
      (node (ref "J1") (pin "31") (pinfunction "31_31") (pintype "passive+no_connect"))
    )
    (net (code "80") (name "unconnected-(J1-Pad35)") (class "Default")
      (node (ref "J1") (pin "35") (pinfunction "35_35") (pintype "passive+no_connect"))
    )
    (net (code "81") (name "unconnected-(J1-Pad37)") (class "Default")
      (node (ref "J1") (pin "37") (pinfunction "37_37") (pintype "passive+no_connect"))
    )
    (net (code "82") (name "unconnected-(J1-Pad38)") (class "Default")
      (node (ref "J1") (pin "38") (pinfunction "38_38") (pintype "passive+no_connect"))
    )
    (net (code "83") (name "unconnected-(J1-Pad39)") (class "Default")
      (node (ref "J1") (pin "39") (pinfunction "39_39") (pintype "passive+no_connect"))
    )
    (net (code "84") (name "unconnected-(J1-Pad40)") (class "Default")
      (node (ref "J1") (pin "40") (pinfunction "40_40") (pintype "passive+no_connect"))
    )
    (net (code "85") (name "unconnected-(J1-Pad41)") (class "Default")
      (node (ref "J1") (pin "41") (pinfunction "41_41") (pintype "passive+no_connect"))
    )
    (net (code "86") (name "unconnected-(J1-Pad42)") (class "Default")
      (node (ref "J1") (pin "42") (pinfunction "42_42") (pintype "passive+no_connect"))
    )
    (net (code "87") (name "unconnected-(J1-Pad43)") (class "Default")
      (node (ref "J1") (pin "43") (pinfunction "43_43") (pintype "passive+no_connect"))
    )
    (net (code "88") (name "unconnected-(J1-Pad45)") (class "Default")
      (node (ref "J1") (pin "45") (pinfunction "45_45") (pintype "passive+no_connect"))
    )
    (net (code "89") (name "unconnected-(J1-Pad46)") (class "Default")
      (node (ref "J1") (pin "46") (pinfunction "46_46") (pintype "passive+no_connect"))
    )
    (net (code "90") (name "unconnected-(J1-Pad47)") (class "Default")
      (node (ref "J1") (pin "47") (pinfunction "47_47") (pintype "passive+no_connect"))
    )
    (net (code "91") (name "unconnected-(J1-Pad48)") (class "Default")
      (node (ref "J1") (pin "48") (pinfunction "48_48") (pintype "passive+no_connect"))
    )
    (net (code "92") (name "unconnected-(J1-Pad49)") (class "Default")
      (node (ref "J1") (pin "49") (pinfunction "49_49") (pintype "passive+no_connect"))
    )
    (net (code "93") (name "unconnected-(J1-Pad51)") (class "Default")
      (node (ref "J1") (pin "51") (pinfunction "51_51") (pintype "passive+no_connect"))
    )
    (net (code "94") (name "unconnected-(J1-Pad52)") (class "Default")
      (node (ref "J1") (pin "52") (pinfunction "52_52") (pintype "passive+no_connect"))
    )
    (net (code "95") (name "unconnected-(J1-Pad53)") (class "Default")
      (node (ref "J1") (pin "53") (pinfunction "53_53") (pintype "passive+no_connect"))
    )
    (net (code "96") (name "unconnected-(J1-Pad54)") (class "Default")
      (node (ref "J1") (pin "54") (pinfunction "54_54") (pintype "passive+no_connect"))
    )
    (net (code "97") (name "unconnected-(J1-Pad55)") (class "Default")
      (node (ref "J1") (pin "55") (pinfunction "55_55") (pintype "passive+no_connect"))
    )
    (net (code "98") (name "unconnected-(J1-Pad57)") (class "Default")
      (node (ref "J1") (pin "57") (pinfunction "57_57") (pintype "passive+no_connect"))
    )
    (net (code "99") (name "unconnected-(J2-Pad2)") (class "Default")
      (node (ref "J2") (pin "2") (pinfunction "2_2") (pintype "passive+no_connect"))
    )
    (net (code "100") (name "unconnected-(J2-Pad3)") (class "Default")
      (node (ref "J2") (pin "3") (pinfunction "3_3") (pintype "passive+no_connect"))
    )
    (net (code "101") (name "unconnected-(J2-Pad4)") (class "Default")
      (node (ref "J2") (pin "4") (pinfunction "4_4") (pintype "passive+no_connect"))
    )
    (net (code "102") (name "unconnected-(J2-Pad5)") (class "Default")
      (node (ref "J2") (pin "5") (pinfunction "5_5") (pintype "passive+no_connect"))
    )
    (net (code "103") (name "unconnected-(J2-Pad6)") (class "Default")
      (node (ref "J2") (pin "6") (pinfunction "6_6") (pintype "passive+no_connect"))
    )
    (net (code "104") (name "unconnected-(J2-Pad7)") (class "Default")
      (node (ref "J2") (pin "7") (pinfunction "7_7") (pintype "passive+no_connect"))
    )
    (net (code "105") (name "unconnected-(J2-Pad8)") (class "Default")
      (node (ref "J2") (pin "8") (pinfunction "8_8") (pintype "passive+no_connect"))
    )
    (net (code "106") (name "unconnected-(J2-Pad9)") (class "Default")
      (node (ref "J2") (pin "9") (pinfunction "9_9") (pintype "passive+no_connect"))
    )
    (net (code "107") (name "unconnected-(J2-Pad10)") (class "Default")
      (node (ref "J2") (pin "10") (pinfunction "10_10") (pintype "passive+no_connect"))
    )
    (net (code "108") (name "unconnected-(J2-Pad11)") (class "Default")
      (node (ref "J2") (pin "11") (pinfunction "11_11") (pintype "passive+no_connect"))
    )
    (net (code "109") (name "unconnected-(J2-Pad13)") (class "Default")
      (node (ref "J2") (pin "13") (pinfunction "13_13") (pintype "passive+no_connect"))
    )
    (net (code "110") (name "unconnected-(J2-Pad15)") (class "Default")
      (node (ref "J2") (pin "15") (pinfunction "15_15") (pintype "passive+no_connect"))
    )
    (net (code "111") (name "unconnected-(J2-Pad17)") (class "Default")
      (node (ref "J2") (pin "17") (pinfunction "17_17") (pintype "passive+no_connect"))
    )
    (net (code "112") (name "unconnected-(J2-Pad18)") (class "Default")
      (node (ref "J2") (pin "18") (pinfunction "18_18") (pintype "passive+no_connect"))
    )
    (net (code "113") (name "unconnected-(J2-Pad19)") (class "Default")
      (node (ref "J2") (pin "19") (pinfunction "19_19") (pintype "passive+no_connect"))
    )
    (net (code "114") (name "unconnected-(J2-Pad20)") (class "Default")
      (node (ref "J2") (pin "20") (pinfunction "20_20") (pintype "passive+no_connect"))
    )
    (net (code "115") (name "unconnected-(J2-Pad21)") (class "Default")
      (node (ref "J2") (pin "21") (pinfunction "21_21") (pintype "passive+no_connect"))
    )
    (net (code "116") (name "unconnected-(J2-Pad22)") (class "Default")
      (node (ref "J2") (pin "22") (pinfunction "22_22") (pintype "passive+no_connect"))
    )
    (net (code "117") (name "unconnected-(J2-Pad24)") (class "Default")
      (node (ref "J2") (pin "24") (pinfunction "24_24") (pintype "passive+no_connect"))
    )
    (net (code "118") (name "unconnected-(J2-Pad25)") (class "Default")
      (node (ref "J2") (pin "25") (pinfunction "25_25") (pintype "passive+no_connect"))
    )
    (net (code "119") (name "unconnected-(J2-Pad26)") (class "Default")
      (node (ref "J2") (pin "26") (pinfunction "26_26") (pintype "passive+no_connect"))
    )
    (net (code "120") (name "unconnected-(J2-Pad27)") (class "Default")
      (node (ref "J2") (pin "27") (pinfunction "27_27") (pintype "passive+no_connect"))
    )
    (net (code "121") (name "unconnected-(J2-Pad29)") (class "Default")
      (node (ref "J2") (pin "29") (pinfunction "29_29") (pintype "passive+no_connect"))
    )
    (net (code "122") (name "unconnected-(J2-Pad30)") (class "Default")
      (node (ref "J2") (pin "30") (pinfunction "30_30") (pintype "passive+no_connect"))
    )
    (net (code "123") (name "unconnected-(J2-Pad31)") (class "Default")
      (node (ref "J2") (pin "31") (pinfunction "31_31") (pintype "passive+no_connect"))
    )
    (net (code "124") (name "unconnected-(J2-Pad35)") (class "Default")
      (node (ref "J2") (pin "35") (pinfunction "35_35") (pintype "passive+no_connect"))
    )
    (net (code "125") (name "unconnected-(J2-Pad37)") (class "Default")
      (node (ref "J2") (pin "37") (pinfunction "37_37") (pintype "passive+no_connect"))
    )
    (net (code "126") (name "unconnected-(J2-Pad38)") (class "Default")
      (node (ref "J2") (pin "38") (pinfunction "38_38") (pintype "passive+no_connect"))
    )
    (net (code "127") (name "unconnected-(J2-Pad40)") (class "Default")
      (node (ref "J2") (pin "40") (pinfunction "40_40") (pintype "passive+no_connect"))
    )
    (net (code "128") (name "unconnected-(J2-Pad41)") (class "Default")
      (node (ref "J2") (pin "41") (pinfunction "41_41") (pintype "passive+no_connect"))
    )
    (net (code "129") (name "unconnected-(J2-Pad42)") (class "Default")
      (node (ref "J2") (pin "42") (pinfunction "42_42") (pintype "passive+no_connect"))
    )
    (net (code "130") (name "unconnected-(J2-Pad43)") (class "Default")
      (node (ref "J2") (pin "43") (pinfunction "43_43") (pintype "passive+no_connect"))
    )
    (net (code "131") (name "unconnected-(J2-Pad45)") (class "Default")
      (node (ref "J2") (pin "45") (pinfunction "45_45") (pintype "passive+no_connect"))
    )
    (net (code "132") (name "unconnected-(J2-Pad46)") (class "Default")
      (node (ref "J2") (pin "46") (pinfunction "46_46") (pintype "passive+no_connect"))
    )
    (net (code "133") (name "unconnected-(J2-Pad47)") (class "Default")
      (node (ref "J2") (pin "47") (pinfunction "47_47") (pintype "passive+no_connect"))
    )
    (net (code "134") (name "unconnected-(J2-Pad48)") (class "Default")
      (node (ref "J2") (pin "48") (pinfunction "48_48") (pintype "passive+no_connect"))
    )
    (net (code "135") (name "unconnected-(J2-Pad49)") (class "Default")
      (node (ref "J2") (pin "49") (pinfunction "49_49") (pintype "passive+no_connect"))
    )
    (net (code "136") (name "unconnected-(J2-Pad51)") (class "Default")
      (node (ref "J2") (pin "51") (pinfunction "51_51") (pintype "passive+no_connect"))
    )
    (net (code "137") (name "unconnected-(J2-Pad52)") (class "Default")
      (node (ref "J2") (pin "52") (pinfunction "52_52") (pintype "passive+no_connect"))
    )
    (net (code "138") (name "unconnected-(J2-Pad53)") (class "Default")
      (node (ref "J2") (pin "53") (pinfunction "53_53") (pintype "passive+no_connect"))
    )
    (net (code "139") (name "unconnected-(J2-Pad54)") (class "Default")
      (node (ref "J2") (pin "54") (pinfunction "54_54") (pintype "passive+no_connect"))
    )
    (net (code "140") (name "unconnected-(J2-Pad55)") (class "Default")
      (node (ref "J2") (pin "55") (pinfunction "55_55") (pintype "passive+no_connect"))
    )
    (net (code "141") (name "unconnected-(J2-Pad56)") (class "Default")
      (node (ref "J2") (pin "56") (pinfunction "56_56") (pintype "passive+no_connect"))
    )
    (net (code "142") (name "unconnected-(J2-Pad57)") (class "Default")
      (node (ref "J2") (pin "57") (pinfunction "57_57") (pintype "passive+no_connect"))
    )
    (net (code "143") (name "unconnected-(J2-Pad58)") (class "Default")
      (node (ref "J2") (pin "58") (pinfunction "58_58") (pintype "passive+no_connect"))
    )
    (net (code "144") (name "unconnected-(J2-Pad59)") (class "Default")
      (node (ref "J2") (pin "59") (pinfunction "59_59") (pintype "passive+no_connect"))
    )
    (net (code "145") (name "unconnected-(J2-Pad60)") (class "Default")
      (node (ref "J2") (pin "60") (pinfunction "60_60") (pintype "passive+no_connect"))
    )
  )
)
